# minesp.net
KiCad netlist of a schematic drawn in EAGLE
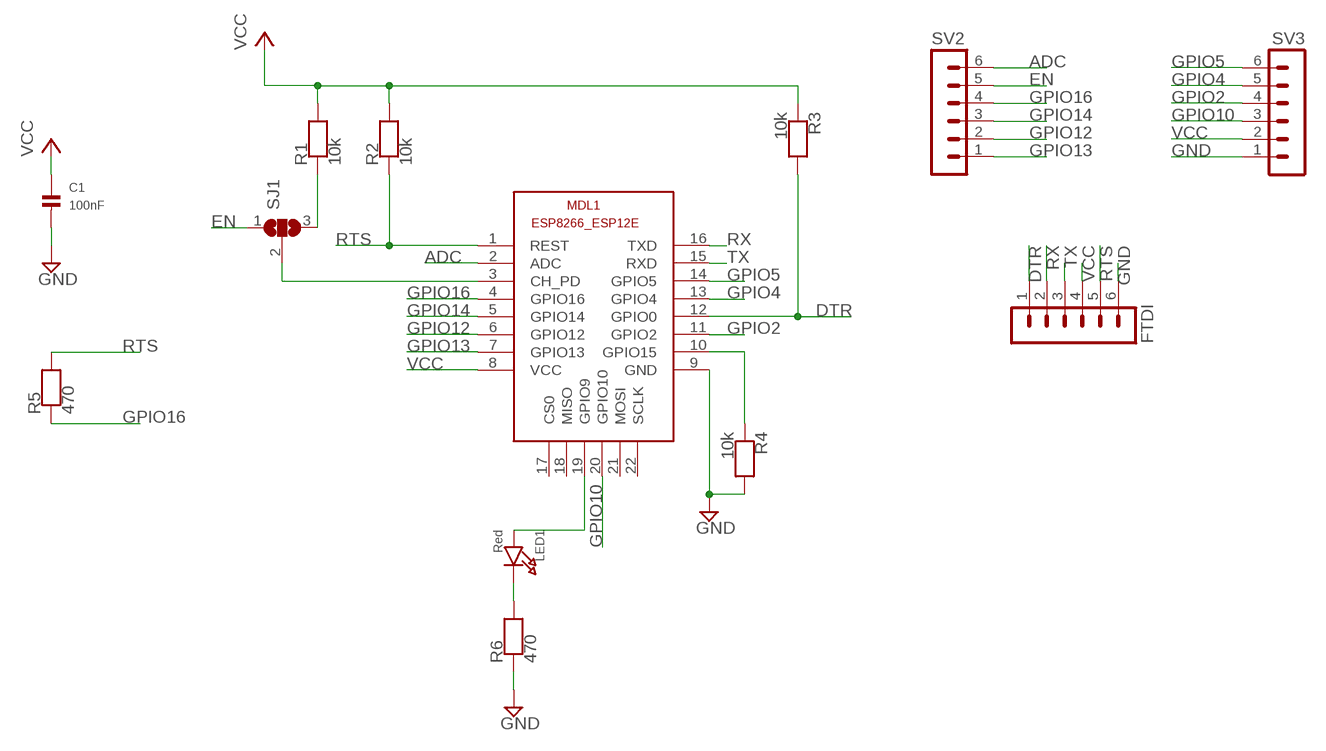
[diagram p0: schematic, sheet 1]

(export (version "E")
  (design (tool "Eeschema 10.0.6"))
  (components
    (comp (ref "C1")
      (value "100nF")
      (footprint "eagle-import:0805")
      (libsource (lib "eagle-import") (part "CAP_CERAMIC0805"))
    )
    (comp (ref "FTDI")
      (value "MA06-1")
      (footprint "eagle-import:MA06-1")
      (libsource (lib "eagle-import") (part "MA06-1"))
    )
    (comp (ref "LED1")
      (value "Red")
      (footprint "eagle-import:CHIPLED_0805")
      (libsource (lib "eagle-import") (part "LED0805"))
    )
    (comp (ref "MDL1")
      (value "ESP8266-12EESP8266-ESP12E")
      (footprint "eagle-import:ESP8266-ESP12E")
      (libsource (lib "eagle-import") (part "ESP8266-12EESP8266-ESP12E"))
    )
    (comp (ref "R1")
      (value "10k")
      (footprint "eagle-import:0805")
      (libsource (lib "eagle-import") (part "RESISTOR0805"))
    )
    (comp (ref "R2")
      (value "10k")
      (footprint "eagle-import:0805")
      (libsource (lib "eagle-import") (part "RESISTOR0805"))
    )
    (comp (ref "R3")
      (value "10k")
      (footprint "eagle-import:0805")
      (libsource (lib "eagle-import") (part "RESISTOR0805"))
    )
    (comp (ref "R4")
      (value "10k")
      (footprint "eagle-import:0805")
      (libsource (lib "eagle-import") (part "RESISTOR0805"))
    )
    (comp (ref "R5")
      (value "470")
      (footprint "eagle-import:0805")
      (libsource (lib "eagle-import") (part "RESISTOR0805"))
    )
    (comp (ref "R6")
      (value "470")
      (footprint "eagle-import:0805")
      (libsource (lib "eagle-import") (part "RESISTOR0805"))
    )
    (comp (ref "SJ1")
      (value "SJ2W")
      (footprint "eagle-import:SJ_2")
      (libsource (lib "eagle-import") (part "SJ2W"))
    )
    (comp (ref "SV2")
      (value "MA06-1")
      (footprint "eagle-import:MA06-1")
      (libsource (lib "eagle-import") (part "MA06-1"))
    )
    (comp (ref "SV3")
      (value "MA06-1")
      (footprint "eagle-import:MA06-1")
      (libsource (lib "eagle-import") (part "MA06-1"))
    )
  )
  (nets
    (net (code "1") (name "/ADC") (class "Default")
      (node (ref "MDL1") (pin "2") (pinfunction "ADC_2") (pintype "bidirectional"))
      (node (ref "SV2") (pin "6") (pinfunction "6_6") (pintype "passive"))
    )
    (net (code "2") (name "/DTR") (class "Default")
      (node (ref "FTDI") (pin "1") (pinfunction "1_1") (pintype "passive"))
      (node (ref "MDL1") (pin "12") (pinfunction "GPIO0_12") (pintype "bidirectional"))
      (node (ref "R3") (pin "2") (pinfunction "2_2") (pintype "passive"))
    )
    (net (code "3") (name "/EN") (class "Default")
      (node (ref "SJ1") (pin "1") (pinfunction "1_1") (pintype "passive"))
      (node (ref "SV2") (pin "5") (pinfunction "5_5") (pintype "passive"))
    )
    (net (code "4") (name "/GPIO2") (class "Default")
      (node (ref "MDL1") (pin "11") (pinfunction "GPIO2_11") (pintype "bidirectional"))
      (node (ref "SV3") (pin "4") (pinfunction "4_4") (pintype "passive"))
    )
    (net (code "5") (name "/GPIO4") (class "Default")
      (node (ref "MDL1") (pin "13") (pinfunction "GPIO4_13") (pintype "bidirectional"))
      (node (ref "SV3") (pin "5") (pinfunction "5_5") (pintype "passive"))
    )
    (net (code "6") (name "/GPIO5") (class "Default")
      (node (ref "MDL1") (pin "14") (pinfunction "GPIO5_14") (pintype "bidirectional"))
      (node (ref "SV3") (pin "6") (pinfunction "6_6") (pintype "passive"))
    )
    (net (code "7") (name "/GPIO10") (class "Default")
      (node (ref "MDL1") (pin "20") (pinfunction "GPIO10_20") (pintype "bidirectional"))
      (node (ref "SV3") (pin "3") (pinfunction "3_3") (pintype "passive"))
    )
    (net (code "8") (name "/GPIO12") (class "Default")
      (node (ref "MDL1") (pin "6") (pinfunction "GPIO12_6") (pintype "bidirectional"))
      (node (ref "SV2") (pin "2") (pinfunction "2_2") (pintype "passive"))
    )
    (net (code "9") (name "/GPIO13") (class "Default")
      (node (ref "MDL1") (pin "7") (pinfunction "GPIO13_7") (pintype "bidirectional"))
      (node (ref "SV2") (pin "1") (pinfunction "1_1") (pintype "passive"))
    )
    (net (code "10") (name "/GPIO14") (class "Default")
      (node (ref "MDL1") (pin "5") (pinfunction "GPIO14_5") (pintype "bidirectional"))
      (node (ref "SV2") (pin "3") (pinfunction "3_3") (pintype "passive"))
    )
    (net (code "11") (name "/GPIO16") (class "Default")
      (node (ref "MDL1") (pin "4") (pinfunction "GPIO16_4") (pintype "bidirectional"))
      (node (ref "R5") (pin "1") (pinfunction "1_1") (pintype "passive"))
      (node (ref "SV2") (pin "4") (pinfunction "4_4") (pintype "passive"))
    )
    (net (code "12") (name "/RTS") (class "Default")
      (node (ref "FTDI") (pin "5") (pinfunction "5_5") (pintype "passive"))
      (node (ref "MDL1") (pin "1") (pinfunction "REST_1") (pintype "bidirectional"))
      (node (ref "R2") (pin "1") (pinfunction "1_1") (pintype "passive"))
      (node (ref "R5") (pin "2") (pinfunction "2_2") (pintype "passive"))
    )
    (net (code "13") (name "/RX") (class "Default")
      (node (ref "FTDI") (pin "2") (pinfunction "2_2") (pintype "passive"))
      (node (ref "MDL1") (pin "16") (pinfunction "TXD_16") (pintype "bidirectional"))
    )
    (net (code "14") (name "/TX") (class "Default")
      (node (ref "FTDI") (pin "3") (pinfunction "3_3") (pintype "passive"))
      (node (ref "MDL1") (pin "15") (pinfunction "RXD_15") (pintype "bidirectional"))
    )
    (net (code "15") (name "GND") (class "Default")
      (node (ref "C1") (pin "2") (pinfunction "P$2_2") (pintype "passive"))
      (node (ref "FTDI") (pin "6") (pinfunction "6_6") (pintype "passive"))
      (node (ref "MDL1") (pin "9") (pinfunction "GND_9") (pintype "bidirectional"))
      (node (ref "R4") (pin "2") (pinfunction "2_2") (pintype "passive"))
      (node (ref "R6") (pin "1") (pinfunction "1_1") (pintype "passive"))
      (node (ref "SV3") (pin "1") (pinfunction "1_1") (pintype "passive"))
    )
    (net (code "16") (name "Net-(LED1-PadC)") (class "Default")
      (node (ref "LED1") (pin "C") (pinfunction "C_C") (pintype "passive"))
      (node (ref "R6") (pin "2") (pinfunction "2_2") (pintype "passive"))
    )
    (net (code "17") (name "Net-(MDL1-CH_PD)") (class "Default")
      (node (ref "MDL1") (pin "3") (pinfunction "CH_PD_3") (pintype "bidirectional"))
      (node (ref "SJ1") (pin "2") (pinfunction "2_2") (pintype "passive"))
    )
    (net (code "18") (name "Net-(MDL1-GPIO9)") (class "Default")
      (node (ref "LED1") (pin "A") (pinfunction "A_A") (pintype "passive"))
      (node (ref "MDL1") (pin "19") (pinfunction "GPIO9_19") (pintype "bidirectional"))
    )
    (net (code "19") (name "Net-(MDL1-GPIO15)") (class "Default")
      (node (ref "MDL1") (pin "10") (pinfunction "GPIO15_10") (pintype "bidirectional"))
      (node (ref "R4") (pin "1") (pinfunction "1_1") (pintype "passive"))
    )
    (net (code "20") (name "Net-(R1-Pad1)") (class "Default")
      (node (ref "R1") (pin "1") (pinfunction "1_1") (pintype "passive"))
      (node (ref "SJ1") (pin "3") (pinfunction "3_3") (pintype "passive"))
    )
    (net (code "21") (name "VCC") (class "Default")
      (node (ref "C1") (pin "1") (pinfunction "P$1_1") (pintype "passive"))
      (node (ref "FTDI") (pin "4") (pinfunction "4_4") (pintype "passive"))
      (node (ref "MDL1") (pin "8") (pinfunction "VCC_8") (pintype "bidirectional"))
      (node (ref "R1") (pin "2") (pinfunction "2_2") (pintype "passive"))
      (node (ref "R2") (pin "2") (pinfunction "2_2") (pintype "passive"))
      (node (ref "R3") (pin "1") (pinfunction "1_1") (pintype "passive"))
      (node (ref "SV3") (pin "2") (pinfunction "2_2") (pintype "passive"))
    )
    (net (code "22") (name "unconnected-(MDL1-CS0-Pad17)") (class "Default")
      (node (ref "MDL1") (pin "17") (pinfunction "CS0_17") (pintype "bidirectional"))
    )
    (net (code "23") (name "unconnected-(MDL1-MISO-Pad18)") (class "Default")
      (node (ref "MDL1") (pin "18") (pinfunction "MISO_18") (pintype "bidirectional"))
    )
    (net (code "24") (name "unconnected-(MDL1-MOSI-Pad21)") (class "Default")
      (node (ref "MDL1") (pin "21") (pinfunction "MOSI_21") (pintype "bidirectional"))
    )
    (net (code "25") (name "unconnected-(MDL1-SCLK-Pad22)") (class "Default")
      (node (ref "MDL1") (pin "22") (pinfunction "SCLK_22") (pintype "bidirectional"))
    )
  )
)
